# IRis_-_Master_Schematic.net
KiCad netlist of a schematic drawn in EAGLE
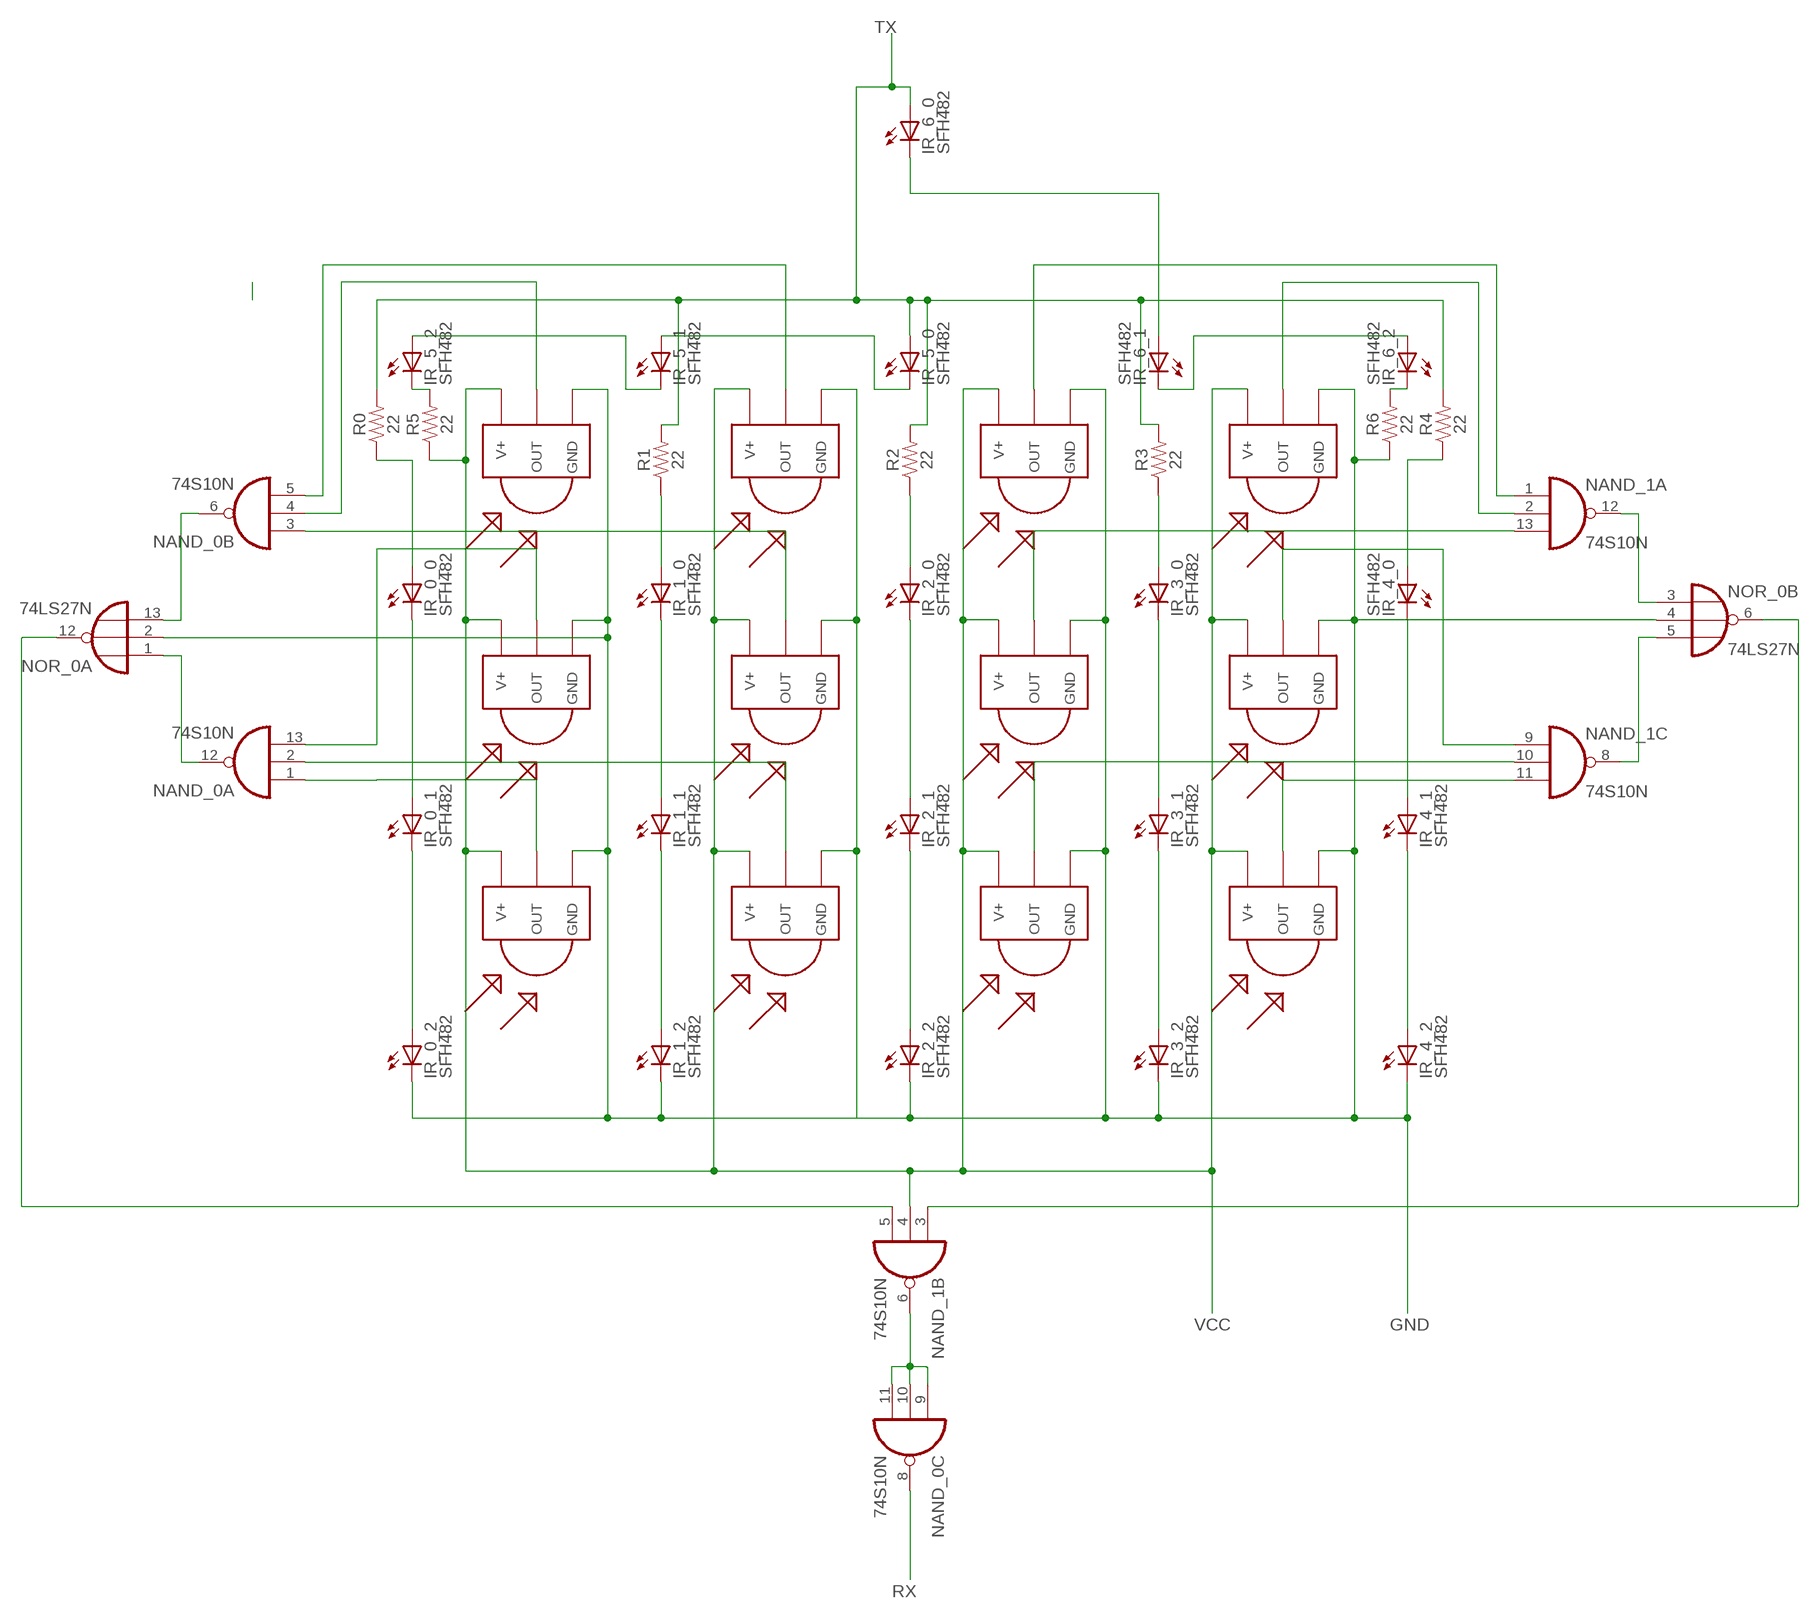
[diagram p0: schematic, sheet 1]

(export (version "E")
  (design (tool "Eeschema 10.0.6"))
  (components
    (comp (ref "IR_0_0")
      (value "SFH482")
      (footprint "eagle-import:SFH482")
      (libsource (lib "eagle-import") (part "SFH482"))
    )
    (comp (ref "IR_0_1")
      (value "SFH482")
      (footprint "eagle-import:SFH482")
      (libsource (lib "eagle-import") (part "SFH482"))
    )
    (comp (ref "IR_0_2")
      (value "SFH482")
      (footprint "eagle-import:SFH482")
      (libsource (lib "eagle-import") (part "SFH482"))
    )
    (comp (ref "IR_1_0")
      (value "SFH482")
      (footprint "eagle-import:SFH482")
      (libsource (lib "eagle-import") (part "SFH482"))
    )
    (comp (ref "IR_1_1")
      (value "SFH482")
      (footprint "eagle-import:SFH482")
      (libsource (lib "eagle-import") (part "SFH482"))
    )
    (comp (ref "IR_1_2")
      (value "SFH482")
      (footprint "eagle-import:SFH482")
      (libsource (lib "eagle-import") (part "SFH482"))
    )
    (comp (ref "IR_2_0")
      (value "SFH482")
      (footprint "eagle-import:SFH482")
      (libsource (lib "eagle-import") (part "SFH482"))
    )
    (comp (ref "IR_2_1")
      (value "SFH482")
      (footprint "eagle-import:SFH482")
      (libsource (lib "eagle-import") (part "SFH482"))
    )
    (comp (ref "IR_2_2")
      (value "SFH482")
      (footprint "eagle-import:SFH482")
      (libsource (lib "eagle-import") (part "SFH482"))
    )
    (comp (ref "IR_3_0")
      (value "SFH482")
      (footprint "eagle-import:SFH482")
      (libsource (lib "eagle-import") (part "SFH482"))
    )
    (comp (ref "IR_3_1")
      (value "SFH482")
      (footprint "eagle-import:SFH482")
      (libsource (lib "eagle-import") (part "SFH482"))
    )
    (comp (ref "IR_3_2")
      (value "SFH482")
      (footprint "eagle-import:SFH482")
      (libsource (lib "eagle-import") (part "SFH482"))
    )
    (comp (ref "IR_4_0")
      (value "SFH482")
      (footprint "eagle-import:SFH482")
      (libsource (lib "eagle-import") (part "SFH482"))
    )
    (comp (ref "IR_4_1")
      (value "SFH482")
      (footprint "eagle-import:SFH482")
      (libsource (lib "eagle-import") (part "SFH482"))
    )
    (comp (ref "IR_4_2")
      (value "SFH482")
      (footprint "eagle-import:SFH482")
      (libsource (lib "eagle-import") (part "SFH482"))
    )
    (comp (ref "IR_5_0")
      (value "SFH482")
      (footprint "eagle-import:SFH482")
      (libsource (lib "eagle-import") (part "SFH482"))
    )
    (comp (ref "IR_5_1")
      (value "SFH482")
      (footprint "eagle-import:SFH482")
      (libsource (lib "eagle-import") (part "SFH482"))
    )
    (comp (ref "IR_5_2")
      (value "SFH482")
      (footprint "eagle-import:SFH482")
      (libsource (lib "eagle-import") (part "SFH482"))
    )
    (comp (ref "IR_6_0")
      (value "SFH482")
      (footprint "eagle-import:SFH482")
      (libsource (lib "eagle-import") (part "SFH482"))
    )
    (comp (ref "IR_6_1")
      (value "SFH482")
      (footprint "eagle-import:SFH482")
      (libsource (lib "eagle-import") (part "SFH482"))
    )
    (comp (ref "IR_6_2")
      (value "SFH482")
      (footprint "eagle-import:SFH482")
      (libsource (lib "eagle-import") (part "SFH482"))
    )
    (comp (ref "IR_RX_0")
      (value "TSOP1838")
      (footprint "eagle-import:TSOP18XX")
      (libsource (lib "eagle-import") (part "TSOP1838"))
    )
    (comp (ref "IR_RX_1")
      (value "TSOP1838")
      (footprint "eagle-import:TSOP18XX")
      (libsource (lib "eagle-import") (part "TSOP1838"))
    )
    (comp (ref "IR_RX_2")
      (value "TSOP1838")
      (footprint "eagle-import:TSOP18XX")
      (libsource (lib "eagle-import") (part "TSOP1838"))
    )
    (comp (ref "IR_RX_3")
      (value "TSOP1838")
      (footprint "eagle-import:TSOP18XX")
      (libsource (lib "eagle-import") (part "TSOP1838"))
    )
    (comp (ref "IR_RX_4")
      (value "TSOP1838")
      (footprint "eagle-import:TSOP18XX")
      (libsource (lib "eagle-import") (part "TSOP1838"))
    )
    (comp (ref "IR_RX_5")
      (value "TSOP1838")
      (footprint "eagle-import:TSOP18XX")
      (libsource (lib "eagle-import") (part "TSOP1838"))
    )
    (comp (ref "IR_RX_6")
      (value "TSOP1838")
      (footprint "eagle-import:TSOP18XX")
      (libsource (lib "eagle-import") (part "TSOP1838"))
    )
    (comp (ref "IR_RX_7")
      (value "TSOP1838")
      (footprint "eagle-import:TSOP18XX")
      (libsource (lib "eagle-import") (part "TSOP1838"))
    )
    (comp (ref "IR_RX_8")
      (value "TSOP1838")
      (footprint "eagle-import:TSOP18XX")
      (libsource (lib "eagle-import") (part "TSOP1838"))
    )
    (comp (ref "IR_RX_9")
      (value "TSOP1838")
      (footprint "eagle-import:TSOP18XX")
      (libsource (lib "eagle-import") (part "TSOP1838"))
    )
    (comp (ref "IR_RX_10")
      (value "TSOP1838")
      (footprint "eagle-import:TSOP18XX")
      (libsource (lib "eagle-import") (part "TSOP1838"))
    )
    (comp (ref "IR_RX_11")
      (value "TSOP1838")
      (footprint "eagle-import:TSOP18XX")
      (libsource (lib "eagle-import") (part "TSOP1838"))
    )
    (comp (ref "NAND_0")
      (value "74S10N")
      (footprint "eagle-import:DIL14")
      (libsource (lib "eagle-import") (part "7410NS"))
    )
    (comp (ref "NAND_1")
      (value "74S10N")
      (footprint "eagle-import:DIL14")
      (libsource (lib "eagle-import") (part "7410NS"))
    )
    (comp (ref "NOR_0")
      (value "74LS27N")
      (footprint "eagle-import:DIL14")
      (libsource (lib "eagle-import") (part "7427NLS"))
    )
    (comp (ref "R0")
      (value "22")
      (footprint "eagle-import:0402")
      (libsource (lib "eagle-import") (part "22OHM-0402-1/10W-1%"))
    )
    (comp (ref "R1")
      (value "22")
      (footprint "eagle-import:0402")
      (libsource (lib "eagle-import") (part "22OHM-0402-1/10W-1%"))
    )
    (comp (ref "R2")
      (value "22")
      (footprint "eagle-import:0402")
      (libsource (lib "eagle-import") (part "22OHM-0402-1/10W-1%"))
    )
    (comp (ref "R3")
      (value "22")
      (footprint "eagle-import:0402")
      (libsource (lib "eagle-import") (part "22OHM-0402-1/10W-1%"))
    )
    (comp (ref "R4")
      (value "22")
      (footprint "eagle-import:0402")
      (libsource (lib "eagle-import") (part "22OHM-0402-1/10W-1%"))
    )
    (comp (ref "R5")
      (value "22")
      (footprint "eagle-import:0402")
      (libsource (lib "eagle-import") (part "22OHM-0402-1/10W-1%"))
    )
    (comp (ref "R6")
      (value "22")
      (footprint "eagle-import:0402")
      (libsource (lib "eagle-import") (part "22OHM-0402-1/10W-1%"))
    )
  )
  (nets
    (net (code "1") (name "/GND") (class "Default")
      (node (ref "IR_0_2") (pin "K") (pinfunction "C_K") (pintype "passive"))
      (node (ref "IR_1_2") (pin "K") (pinfunction "C_K") (pintype "passive"))
      (node (ref "IR_2_2") (pin "K") (pinfunction "C_K") (pintype "passive"))
      (node (ref "IR_3_2") (pin "K") (pinfunction "C_K") (pintype "passive"))
      (node (ref "IR_4_2") (pin "K") (pinfunction "C_K") (pintype "passive"))
      (node (ref "IR_RX_0") (pin "GND") (pinfunction "GND_GND") (pintype "bidirectional"))
      (node (ref "IR_RX_1") (pin "GND") (pinfunction "GND_GND") (pintype "bidirectional"))
      (node (ref "IR_RX_10") (pin "GND") (pinfunction "GND_GND") (pintype "bidirectional"))
      (node (ref "IR_RX_11") (pin "GND") (pinfunction "GND_GND") (pintype "bidirectional"))
      (node (ref "IR_RX_2") (pin "GND") (pinfunction "GND_GND") (pintype "bidirectional"))
      (node (ref "IR_RX_3") (pin "GND") (pinfunction "GND_GND") (pintype "bidirectional"))
      (node (ref "IR_RX_4") (pin "GND") (pinfunction "GND_GND") (pintype "bidirectional"))
      (node (ref "IR_RX_5") (pin "GND") (pinfunction "GND_GND") (pintype "bidirectional"))
      (node (ref "IR_RX_6") (pin "GND") (pinfunction "GND_GND") (pintype "bidirectional"))
      (node (ref "IR_RX_7") (pin "GND") (pinfunction "GND_GND") (pintype "bidirectional"))
      (node (ref "IR_RX_8") (pin "GND") (pinfunction "GND_GND") (pintype "bidirectional"))
      (node (ref "IR_RX_9") (pin "GND") (pinfunction "GND_GND") (pintype "bidirectional"))
      (node (ref "NOR_0") (pin "2") (pinfunction "I1_2") (pintype "input"))
      (node (ref "NOR_0") (pin "4") (pinfunction "I1_4") (pintype "input"))
      (node (ref "R6") (pin "1") (pinfunction "1_1") (pintype "passive"))
    )
    (net (code "2") (name "/RX") (class "Default")
      (node (ref "NAND_0") (pin "8") (pinfunction "O_8") (pintype "output"))
    )
    (net (code "3") (name "/TX") (class "Default")
      (node (ref "IR_5_0") (pin "A") (pinfunction "A_A") (pintype "passive"))
      (node (ref "IR_6_0") (pin "A") (pinfunction "A_A") (pintype "passive"))
      (node (ref "R0") (pin "2") (pinfunction "2_2") (pintype "passive"))
      (node (ref "R1") (pin "2") (pinfunction "2_2") (pintype "passive"))
      (node (ref "R2") (pin "2") (pinfunction "2_2") (pintype "passive"))
      (node (ref "R3") (pin "2") (pinfunction "2_2") (pintype "passive"))
      (node (ref "R4") (pin "2") (pinfunction "2_2") (pintype "passive"))
    )
    (net (code "4") (name "/VCC") (class "Default")
      (node (ref "IR_RX_0") (pin "VCC") (pinfunction "V+_VCC") (pintype "bidirectional"))
      (node (ref "IR_RX_1") (pin "VCC") (pinfunction "V+_VCC") (pintype "bidirectional"))
      (node (ref "IR_RX_10") (pin "VCC") (pinfunction "V+_VCC") (pintype "bidirectional"))
      (node (ref "IR_RX_11") (pin "VCC") (pinfunction "V+_VCC") (pintype "bidirectional"))
      (node (ref "IR_RX_2") (pin "VCC") (pinfunction "V+_VCC") (pintype "bidirectional"))
      (node (ref "IR_RX_3") (pin "VCC") (pinfunction "V+_VCC") (pintype "bidirectional"))
      (node (ref "IR_RX_4") (pin "VCC") (pinfunction "V+_VCC") (pintype "bidirectional"))
      (node (ref "IR_RX_5") (pin "VCC") (pinfunction "V+_VCC") (pintype "bidirectional"))
      (node (ref "IR_RX_6") (pin "VCC") (pinfunction "V+_VCC") (pintype "bidirectional"))
      (node (ref "IR_RX_7") (pin "VCC") (pinfunction "V+_VCC") (pintype "bidirectional"))
      (node (ref "IR_RX_8") (pin "VCC") (pinfunction "V+_VCC") (pintype "bidirectional"))
      (node (ref "IR_RX_9") (pin "VCC") (pinfunction "V+_VCC") (pintype "bidirectional"))
      (node (ref "NAND_1") (pin "4") (pinfunction "I1_4") (pintype "input"))
      (node (ref "R5") (pin "1") (pinfunction "1_1") (pintype "passive"))
    )
    (net (code "5") (name "Net-(IR_0_0-C)") (class "Default")
      (node (ref "IR_0_0") (pin "K") (pinfunction "C_K") (pintype "passive"))
      (node (ref "IR_0_1") (pin "A") (pinfunction "A_A") (pintype "passive"))
    )
    (net (code "6") (name "Net-(IR_0_0-PadA)") (class "Default")
      (node (ref "IR_0_0") (pin "A") (pinfunction "A_A") (pintype "passive"))
      (node (ref "R0") (pin "1") (pinfunction "1_1") (pintype "passive"))
    )
    (net (code "7") (name "Net-(IR_0_1-C)") (class "Default")
      (node (ref "IR_0_1") (pin "K") (pinfunction "C_K") (pintype "passive"))
      (node (ref "IR_0_2") (pin "A") (pinfunction "A_A") (pintype "passive"))
    )
    (net (code "8") (name "Net-(IR_1_0-C)") (class "Default")
      (node (ref "IR_1_0") (pin "K") (pinfunction "C_K") (pintype "passive"))
      (node (ref "IR_1_1") (pin "A") (pinfunction "A_A") (pintype "passive"))
    )
    (net (code "9") (name "Net-(IR_1_0-PadA)") (class "Default")
      (node (ref "IR_1_0") (pin "A") (pinfunction "A_A") (pintype "passive"))
      (node (ref "R1") (pin "1") (pinfunction "1_1") (pintype "passive"))
    )
    (net (code "10") (name "Net-(IR_1_1-C)") (class "Default")
      (node (ref "IR_1_1") (pin "K") (pinfunction "C_K") (pintype "passive"))
      (node (ref "IR_1_2") (pin "A") (pinfunction "A_A") (pintype "passive"))
    )
    (net (code "11") (name "Net-(IR_2_0-C)") (class "Default")
      (node (ref "IR_2_0") (pin "K") (pinfunction "C_K") (pintype "passive"))
      (node (ref "IR_2_1") (pin "A") (pinfunction "A_A") (pintype "passive"))
    )
    (net (code "12") (name "Net-(IR_2_0-PadA)") (class "Default")
      (node (ref "IR_2_0") (pin "A") (pinfunction "A_A") (pintype "passive"))
      (node (ref "R2") (pin "1") (pinfunction "1_1") (pintype "passive"))
    )
    (net (code "13") (name "Net-(IR_2_1-C)") (class "Default")
      (node (ref "IR_2_1") (pin "K") (pinfunction "C_K") (pintype "passive"))
      (node (ref "IR_2_2") (pin "A") (pinfunction "A_A") (pintype "passive"))
    )
    (net (code "14") (name "Net-(IR_3_0-C)") (class "Default")
      (node (ref "IR_3_0") (pin "K") (pinfunction "C_K") (pintype "passive"))
      (node (ref "IR_3_1") (pin "A") (pinfunction "A_A") (pintype "passive"))
    )
    (net (code "15") (name "Net-(IR_3_0-PadA)") (class "Default")
      (node (ref "IR_3_0") (pin "A") (pinfunction "A_A") (pintype "passive"))
      (node (ref "R3") (pin "1") (pinfunction "1_1") (pintype "passive"))
    )
    (net (code "16") (name "Net-(IR_3_1-C)") (class "Default")
      (node (ref "IR_3_1") (pin "K") (pinfunction "C_K") (pintype "passive"))
      (node (ref "IR_3_2") (pin "A") (pinfunction "A_A") (pintype "passive"))
    )
    (net (code "17") (name "Net-(IR_4_0-C)") (class "Default")
      (node (ref "IR_4_0") (pin "K") (pinfunction "C_K") (pintype "passive"))
      (node (ref "IR_4_1") (pin "A") (pinfunction "A_A") (pintype "passive"))
    )
    (net (code "18") (name "Net-(IR_4_0-PadA)") (class "Default")
      (node (ref "IR_4_0") (pin "A") (pinfunction "A_A") (pintype "passive"))
      (node (ref "R4") (pin "1") (pinfunction "1_1") (pintype "passive"))
    )
    (net (code "19") (name "Net-(IR_4_1-C)") (class "Default")
      (node (ref "IR_4_1") (pin "K") (pinfunction "C_K") (pintype "passive"))
      (node (ref "IR_4_2") (pin "A") (pinfunction "A_A") (pintype "passive"))
    )
    (net (code "20") (name "Net-(IR_5_0-C)") (class "Default")
      (node (ref "IR_5_0") (pin "K") (pinfunction "C_K") (pintype "passive"))
      (node (ref "IR_5_1") (pin "A") (pinfunction "A_A") (pintype "passive"))
    )
    (net (code "21") (name "Net-(IR_5_1-C)") (class "Default")
      (node (ref "IR_5_1") (pin "K") (pinfunction "C_K") (pintype "passive"))
      (node (ref "IR_5_2") (pin "A") (pinfunction "A_A") (pintype "passive"))
    )
    (net (code "22") (name "Net-(IR_5_2-C)") (class "Default")
      (node (ref "IR_5_2") (pin "K") (pinfunction "C_K") (pintype "passive"))
      (node (ref "R5") (pin "2") (pinfunction "2_2") (pintype "passive"))
    )
    (net (code "23") (name "Net-(IR_6_0-C)") (class "Default")
      (node (ref "IR_6_0") (pin "K") (pinfunction "C_K") (pintype "passive"))
      (node (ref "IR_6_1") (pin "A") (pinfunction "A_A") (pintype "passive"))
    )
    (net (code "24") (name "Net-(IR_6_1-C)") (class "Default")
      (node (ref "IR_6_1") (pin "K") (pinfunction "C_K") (pintype "passive"))
      (node (ref "IR_6_2") (pin "A") (pinfunction "A_A") (pintype "passive"))
    )
    (net (code "25") (name "Net-(IR_6_2-C)") (class "Default")
      (node (ref "IR_6_2") (pin "K") (pinfunction "C_K") (pintype "passive"))
      (node (ref "R6") (pin "2") (pinfunction "2_2") (pintype "passive"))
    )
    (net (code "26") (name "Net-(NAND_0A-I0)") (class "Default")
      (node (ref "IR_RX_1") (pin "OUT") (pinfunction "OUT_OUT") (pintype "bidirectional"))
      (node (ref "NAND_0") (pin "1") (pinfunction "I0_1") (pintype "input"))
    )
    (net (code "27") (name "Net-(NAND_0A-I1)") (class "Default")
      (node (ref "IR_RX_4") (pin "OUT") (pinfunction "OUT_OUT") (pintype "bidirectional"))
      (node (ref "NAND_0") (pin "2") (pinfunction "I1_2") (pintype "input"))
    )
    (net (code "28") (name "Net-(NAND_0A-I2)") (class "Default")
      (node (ref "IR_RX_0") (pin "OUT") (pinfunction "OUT_OUT") (pintype "bidirectional"))
      (node (ref "NAND_0") (pin "13") (pinfunction "I2_13") (pintype "input"))
    )
    (net (code "29") (name "Net-(NAND_0A-O)") (class "Default")
      (node (ref "NAND_0") (pin "12") (pinfunction "O_12") (pintype "output"))
      (node (ref "NOR_0") (pin "1") (pinfunction "I0_1") (pintype "input"))
    )
    (net (code "30") (name "Net-(NAND_0B-I0)") (class "Default")
      (node (ref "IR_RX_3") (pin "OUT") (pinfunction "OUT_OUT") (pintype "bidirectional"))
      (node (ref "NAND_0") (pin "3") (pinfunction "I0_3") (pintype "input"))
    )
    (net (code "31") (name "Net-(NAND_0B-I1)") (class "Default")
      (node (ref "IR_RX_2") (pin "OUT") (pinfunction "OUT_OUT") (pintype "bidirectional"))
      (node (ref "NAND_0") (pin "4") (pinfunction "I1_4") (pintype "input"))
    )
    (net (code "32") (name "Net-(NAND_0B-I2)") (class "Default")
      (node (ref "IR_RX_5") (pin "OUT") (pinfunction "OUT_OUT") (pintype "bidirectional"))
      (node (ref "NAND_0") (pin "5") (pinfunction "I2_5") (pintype "input"))
    )
    (net (code "33") (name "Net-(NAND_0B-O)") (class "Default")
      (node (ref "NAND_0") (pin "6") (pinfunction "O_6") (pintype "output"))
      (node (ref "NOR_0") (pin "13") (pinfunction "I2_13") (pintype "input"))
    )
    (net (code "34") (name "Net-(NAND_0C-I0)") (class "Default")
      (node (ref "NAND_0") (pin "10") (pinfunction "I1_10") (pintype "input"))
      (node (ref "NAND_0") (pin "11") (pinfunction "I2_11") (pintype "input"))
      (node (ref "NAND_0") (pin "9") (pinfunction "I0_9") (pintype "input"))
      (node (ref "NAND_1") (pin "6") (pinfunction "O_6") (pintype "output"))
    )
    (net (code "35") (name "Net-(NAND_1A-I0)") (class "Default")
      (node (ref "IR_RX_8") (pin "OUT") (pinfunction "OUT_OUT") (pintype "bidirectional"))
      (node (ref "NAND_1") (pin "1") (pinfunction "I0_1") (pintype "input"))
    )
    (net (code "36") (name "Net-(NAND_1A-I1)") (class "Default")
      (node (ref "IR_RX_11") (pin "OUT") (pinfunction "OUT_OUT") (pintype "bidirectional"))
      (node (ref "NAND_1") (pin "2") (pinfunction "I1_2") (pintype "input"))
    )
    (net (code "37") (name "Net-(NAND_1A-I2)") (class "Default")
      (node (ref "IR_RX_6") (pin "OUT") (pinfunction "OUT_OUT") (pintype "bidirectional"))
      (node (ref "NAND_1") (pin "13") (pinfunction "I2_13") (pintype "input"))
    )
    (net (code "38") (name "Net-(NAND_1A-O)") (class "Default")
      (node (ref "NAND_1") (pin "12") (pinfunction "O_12") (pintype "output"))
      (node (ref "NOR_0") (pin "3") (pinfunction "I0_3") (pintype "input"))
    )
    (net (code "39") (name "Net-(NAND_1B-I0)") (class "Default")
      (node (ref "NAND_1") (pin "3") (pinfunction "I0_3") (pintype "input"))
      (node (ref "NOR_0") (pin "6") (pinfunction "O_6") (pintype "output"))
    )
    (net (code "40") (name "Net-(NAND_1B-I2)") (class "Default")
      (node (ref "NAND_1") (pin "5") (pinfunction "I2_5") (pintype "input"))
      (node (ref "NOR_0") (pin "12") (pinfunction "O_12") (pintype "output"))
    )
    (net (code "41") (name "Net-(NAND_1C-I0)") (class "Default")
      (node (ref "IR_RX_9") (pin "OUT") (pinfunction "OUT_OUT") (pintype "bidirectional"))
      (node (ref "NAND_1") (pin "9") (pinfunction "I0_9") (pintype "input"))
    )
    (net (code "42") (name "Net-(NAND_1C-I1)") (class "Default")
      (node (ref "IR_RX_7") (pin "OUT") (pinfunction "OUT_OUT") (pintype "bidirectional"))
      (node (ref "NAND_1") (pin "10") (pinfunction "I1_10") (pintype "input"))
    )
    (net (code "43") (name "Net-(NAND_1C-I2)") (class "Default")
      (node (ref "IR_RX_10") (pin "OUT") (pinfunction "OUT_OUT") (pintype "bidirectional"))
      (node (ref "NAND_1") (pin "11") (pinfunction "I2_11") (pintype "input"))
    )
    (net (code "44") (name "Net-(NAND_1C-O)") (class "Default")
      (node (ref "NAND_1") (pin "8") (pinfunction "O_8") (pintype "output"))
      (node (ref "NOR_0") (pin "5") (pinfunction "I2_5") (pintype "input"))
    )
  )
)
